# Blue_bug.net
KiCad netlist of a schematic drawn in Altium Designer
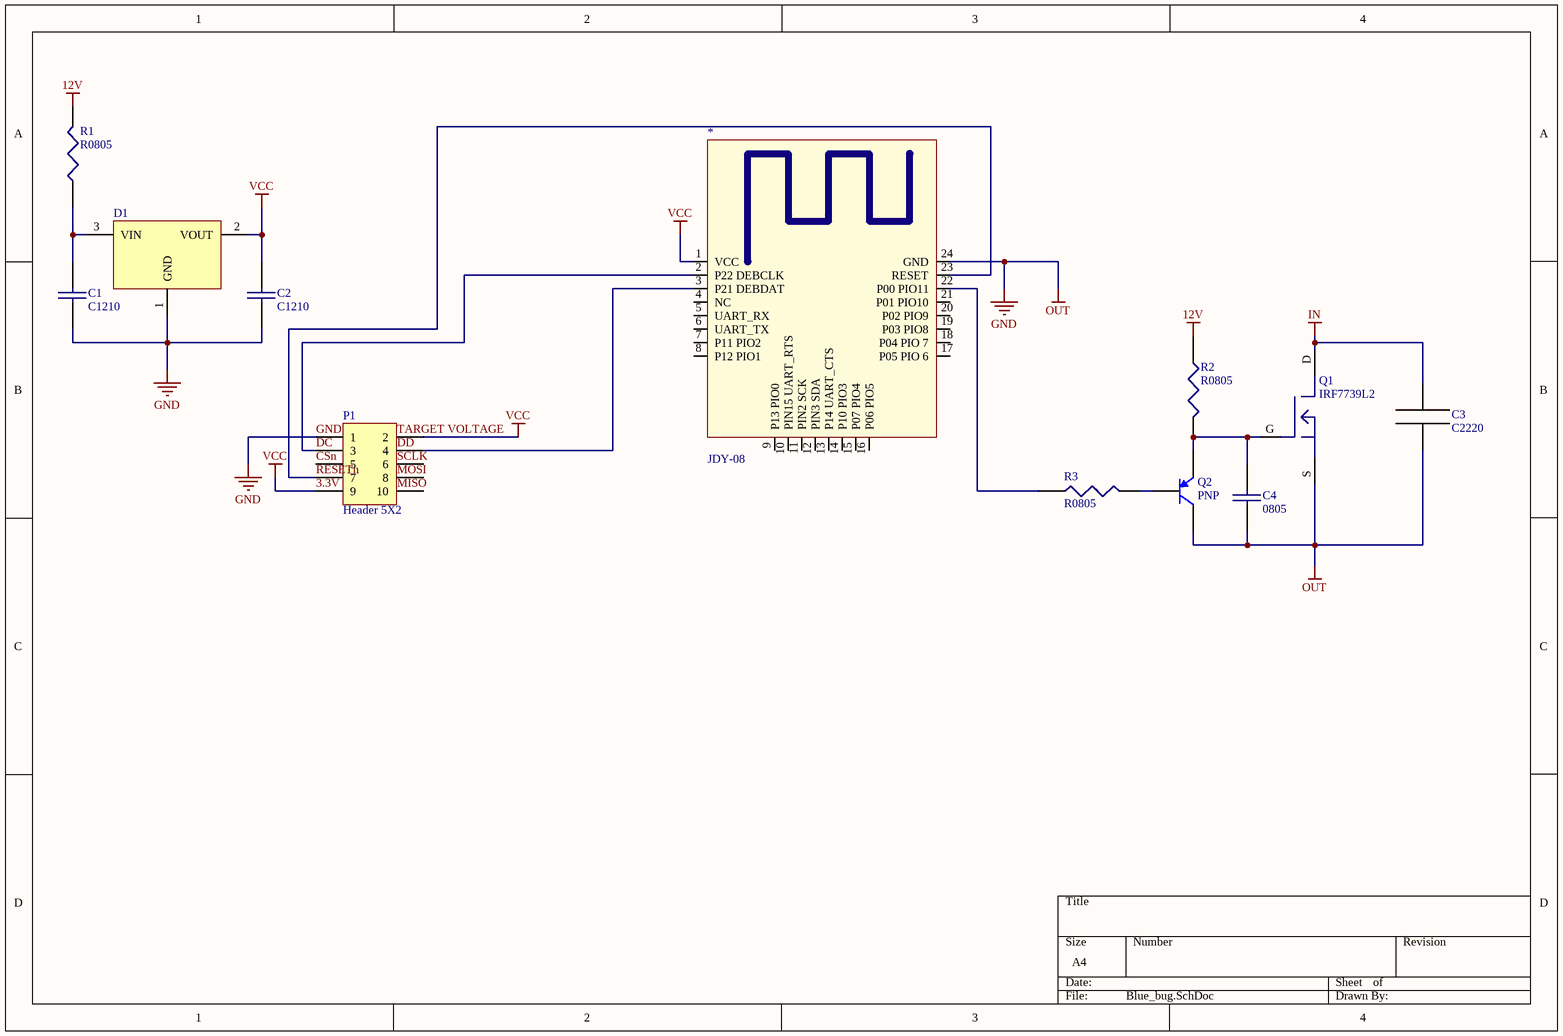
[diagram p0: Blue_bug.SchDoc]

(export (version "E")
  (design (tool "Eeschema 10.0.6"))
  (components
    (comp (ref "*")
      (value "JDY-08")
      (footprint "PCB_Project_6(Powerboard):JDY-08")
      (libsource (lib "PCB_Project_6(Powerboard)") (part "JDY-08"))
    )
    (comp (ref "C1")
      (value "C1210")
      (footprint "Driver_1st:C1210")
      (libsource (lib "Driver_1st") (part "C1210"))
    )
    (comp (ref "C2")
      (value "C1210")
      (footprint "Driver_1st:C1210")
      (libsource (lib "Driver_1st") (part "C1210"))
    )
    (comp (ref "C3")
      (value "С2220")
      (footprint "Driver_1st:C2220")
      (libsource (lib "Driver_1st") (part "С2220"))
    )
    (comp (ref "C4")
      (value "0805")
      (footprint "Driver_1st:C0805")
      (description "Capasitor")
      (libsource (lib "Driver_1st") (part "0805"))
    )
    (comp (ref "D1")
      (value "AMS1117CD_3.3")
      (footprint "PCB_Project_6(Powerboard):SOT223")
      (libsource (lib "PCB_Project_6(Powerboard)") (part "AMS1117CD_3.3"))
    )
    (comp (ref "P1")
      (value "Header 5X2")
      (footprint "HDR2X5")
      (description "Header, 5-Pin, Dual row")
      (fields (field (name "PUBLISHER") "Altium Limited"))
      (libsource (lib "Miscellaneous Connectors") (part "Header 5X2"))
    )
    (comp (ref "Q1")
      (value "IRF7739L2")
      (footprint "PCB_Project_6(Powerboard):DirFET L8")
      (libsource (lib "PCB_Project_6(Powerboard)") (part "IRF7739L2"))
    )
    (comp (ref "Q2")
      (value "PNP")
      (footprint "SOT-23B_N")
      (description "PNP Bipolar Transistor")
      (fields (field (name "PUBLISHER") "Altium Limited"))
      (libsource (lib "Miscellaneous Devices") (part "PNP"))
    )
    (comp (ref "R1")
      (value "R0805")
      (footprint "Driver_1st:R0805")
      (libsource (lib "Driver_1st") (part "R0805"))
    )
    (comp (ref "R2")
      (value "R0805")
      (footprint "Driver_1st:R0805")
      (libsource (lib "Driver_1st") (part "R0805"))
    )
    (comp (ref "R3")
      (value "R0805")
      (footprint "Driver_1st:R0805")
      (libsource (lib "Driver_1st") (part "R0805"))
    )
  )
  (nets
    (net (code "1") (name "/CSn") (class "Default")
      (node (ref "P1") (pin "5") (pinfunction "5_5") (pintype "passive"))
    )
    (net (code "2") (name "/DC") (class "Default")
      (node (ref "*") (pin "2") (pinfunction "P22_DEBCLK_2") (pintype "passive"))
      (node (ref "P1") (pin "3") (pinfunction "3_3") (pintype "passive"))
    )
    (net (code "6") (name "/RESETn") (class "Default")
      (node (ref "*") (pin "23") (pinfunction "RESET_23") (pintype "passive"))
      (node (ref "P1") (pin "7") (pinfunction "7_7") (pintype "passive"))
    )
    (net (code "9") (name "12V") (class "Default")
      (node (ref "R1") (pin "1") (pinfunction "1_1") (pintype "passive"))
      (node (ref "R2") (pin "2") (pinfunction "2_2") (pintype "passive"))
    )
    (net (code "10") (name "GND") (class "Default")
      (node (ref "*") (pin "24") (pinfunction "GND_24") (pintype "passive"))
      (node (ref "C1") (pin "1") (pinfunction "1_1") (pintype "passive"))
      (node (ref "C2") (pin "1") (pinfunction "1_1") (pintype "passive"))
      (node (ref "C3") (pin "1") (pinfunction "1_1") (pintype "passive"))
      (node (ref "C4") (pin "1") (pinfunction "1_1") (pintype "passive"))
      (node (ref "D1") (pin "1") (pinfunction "GND_1") (pintype "passive"))
      (node (ref "P1") (pin "1") (pinfunction "1_1") (pintype "passive"))
      (node (ref "Q1") (pin "S") (pinfunction "3_S") (pintype "passive"))
      (node (ref "Q2") (pin "1") (pinfunction "C_1") (pintype "passive"))
    )
    (net (code "11") (name "IN") (class "Default")
      (node (ref "C3") (pin "2") (pinfunction "2_2") (pintype "passive"))
      (node (ref "Q1") (pin "D") (pinfunction "4_D") (pintype "passive"))
    )
    (net (code "12") (name "Net-(*-P00_PIO11)") (class "Default")
      (node (ref "*") (pin "22") (pinfunction "P00_PIO11_22") (pintype "passive"))
      (node (ref "R3") (pin "2") (pinfunction "2_2") (pintype "passive"))
    )
    (net (code "13") (name "Net-(*-P21_DEBDAT)") (class "Default")
      (node (ref "*") (pin "3") (pinfunction "P21_DEBDAT_3") (pintype "passive"))
      (node (ref "P1") (pin "4") (pinfunction "4_4") (pintype "passive"))
    )
    (net (code "14") (name "Net-(D1-VIN)") (class "Default")
      (node (ref "C1") (pin "2") (pinfunction "2_2") (pintype "passive"))
      (node (ref "D1") (pin "3") (pinfunction "VIN_3") (pintype "passive"))
      (node (ref "R1") (pin "2") (pinfunction "2_2") (pintype "passive"))
    )
    (net (code "15") (name "Net-(Q1-1)") (class "Default")
      (node (ref "C4") (pin "2") (pinfunction "2_2") (pintype "passive"))
      (node (ref "Q1") (pin "G") (pinfunction "1_G") (pintype "passive"))
      (node (ref "Q2") (pin "3") (pinfunction "E_3") (pintype "passive"))
      (node (ref "R2") (pin "1") (pinfunction "1_1") (pintype "passive"))
    )
    (net (code "16") (name "Net-(Q2-B)") (class "Default")
      (node (ref "Q2") (pin "2") (pinfunction "B_2") (pintype "passive"))
      (node (ref "R3") (pin "1") (pinfunction "1_1") (pintype "passive"))
    )
    (net (code "17") (name "VCC") (class "Default")
      (node (ref "*") (pin "1") (pinfunction "VCC_1") (pintype "passive"))
      (node (ref "C2") (pin "2") (pinfunction "2_2") (pintype "passive"))
      (node (ref "D1") (pin "2") (pinfunction "VOUT_2") (pintype "passive"))
      (node (ref "P1") (pin "2") (pinfunction "2_2") (pintype "passive"))
      (node (ref "P1") (pin "9") (pinfunction "9_9") (pintype "passive"))
    )
    (net (code "18") (name "unconnected-(*-NC-Pad4)") (class "Default")
      (node (ref "*") (pin "4") (pinfunction "NC_4") (pintype "passive"))
    )
    (net (code "19") (name "unconnected-(*-P01_PIO10-Pad21)") (class "Default")
      (node (ref "*") (pin "21") (pinfunction "P01_PIO10_21") (pintype "passive"))
    )
    (net (code "20") (name "unconnected-(*-P02_PIO9-Pad20)") (class "Default")
      (node (ref "*") (pin "20") (pinfunction "P02_PIO9_20") (pintype "passive"))
    )
    (net (code "21") (name "unconnected-(*-P03_PIO8-Pad19)") (class "Default")
      (node (ref "*") (pin "19") (pinfunction "P03_PIO8_19") (pintype "passive"))
    )
    (net (code "22") (name "unconnected-(*-P04_PIO_7-Pad18)") (class "Default")
      (node (ref "*") (pin "18") (pinfunction "P04_PIO_7_18") (pintype "passive"))
    )
    (net (code "23") (name "unconnected-(*-P05_PIO_6-Pad17)") (class "Default")
      (node (ref "*") (pin "17") (pinfunction "P05_PIO_6_17") (pintype "passive"))
    )
    (net (code "24") (name "unconnected-(*-P06_PIO5-Pad16)") (class "Default")
      (node (ref "*") (pin "16") (pinfunction "P06_PIO5_16") (pintype "passive"))
    )
    (net (code "25") (name "unconnected-(*-P07_PIO4-Pad15)") (class "Default")
      (node (ref "*") (pin "15") (pinfunction "P07_PIO4_15") (pintype "passive"))
    )
    (net (code "26") (name "unconnected-(*-P10_PIO3-Pad14)") (class "Default")
      (node (ref "*") (pin "14") (pinfunction "P10_PIO3_14") (pintype "passive"))
    )
    (net (code "27") (name "unconnected-(*-P11_PIO2-Pad7)") (class "Default")
      (node (ref "*") (pin "7") (pinfunction "P11_PIO2_7") (pintype "passive"))
    )
    (net (code "28") (name "unconnected-(*-P12_PIO1-Pad8)") (class "Default")
      (node (ref "*") (pin "8") (pinfunction "P12_PIO1_8") (pintype "passive"))
    )
    (net (code "29") (name "unconnected-(*-P13_PIO0-Pad9)") (class "Default")
      (node (ref "*") (pin "9") (pinfunction "P13_PIO0_9") (pintype "passive"))
    )
    (net (code "30") (name "unconnected-(*-P14_UART_CTS-Pad13)") (class "Default")
      (node (ref "*") (pin "13") (pinfunction "P14_UART_CTS_13") (pintype "passive"))
    )
    (net (code "31") (name "unconnected-(*-PIN2_SCK-Pad11)") (class "Default")
      (node (ref "*") (pin "11") (pinfunction "PIN2_SCK_11") (pintype "passive"))
    )
    (net (code "32") (name "unconnected-(*-PIN3_SDA-Pad12)") (class "Default")
      (node (ref "*") (pin "12") (pinfunction "PIN3_SDA_12") (pintype "passive"))
    )
    (net (code "33") (name "unconnected-(*-PIN15_UART_RTS-Pad10)") (class "Default")
      (node (ref "*") (pin "10") (pinfunction "PIN15_UART_RTS_10") (pintype "passive"))
    )
    (net (code "34") (name "unconnected-(*-UART_RX-Pad5)") (class "Default")
      (node (ref "*") (pin "5") (pinfunction "UART_RX_5") (pintype "passive"))
    )
    (net (code "35") (name "unconnected-(*-UART_TX-Pad6)") (class "Default")
      (node (ref "*") (pin "6") (pinfunction "UART_TX_6") (pintype "passive"))
    )
    (net (code "36") (name "unconnected-(P1-Pad6)") (class "Default")
      (node (ref "P1") (pin "6") (pinfunction "6_6") (pintype "passive"))
    )
    (net (code "37") (name "unconnected-(P1-Pad8)") (class "Default")
      (node (ref "P1") (pin "8") (pinfunction "8_8") (pintype "passive"))
    )
    (net (code "38") (name "unconnected-(P1-Pad10)") (class "Default")
      (node (ref "P1") (pin "10") (pinfunction "10_10") (pintype "passive"))
    )
  )
)
